# ServoControllerCircuit.net
KiCad netlist of a schematic drawn in EAGLE
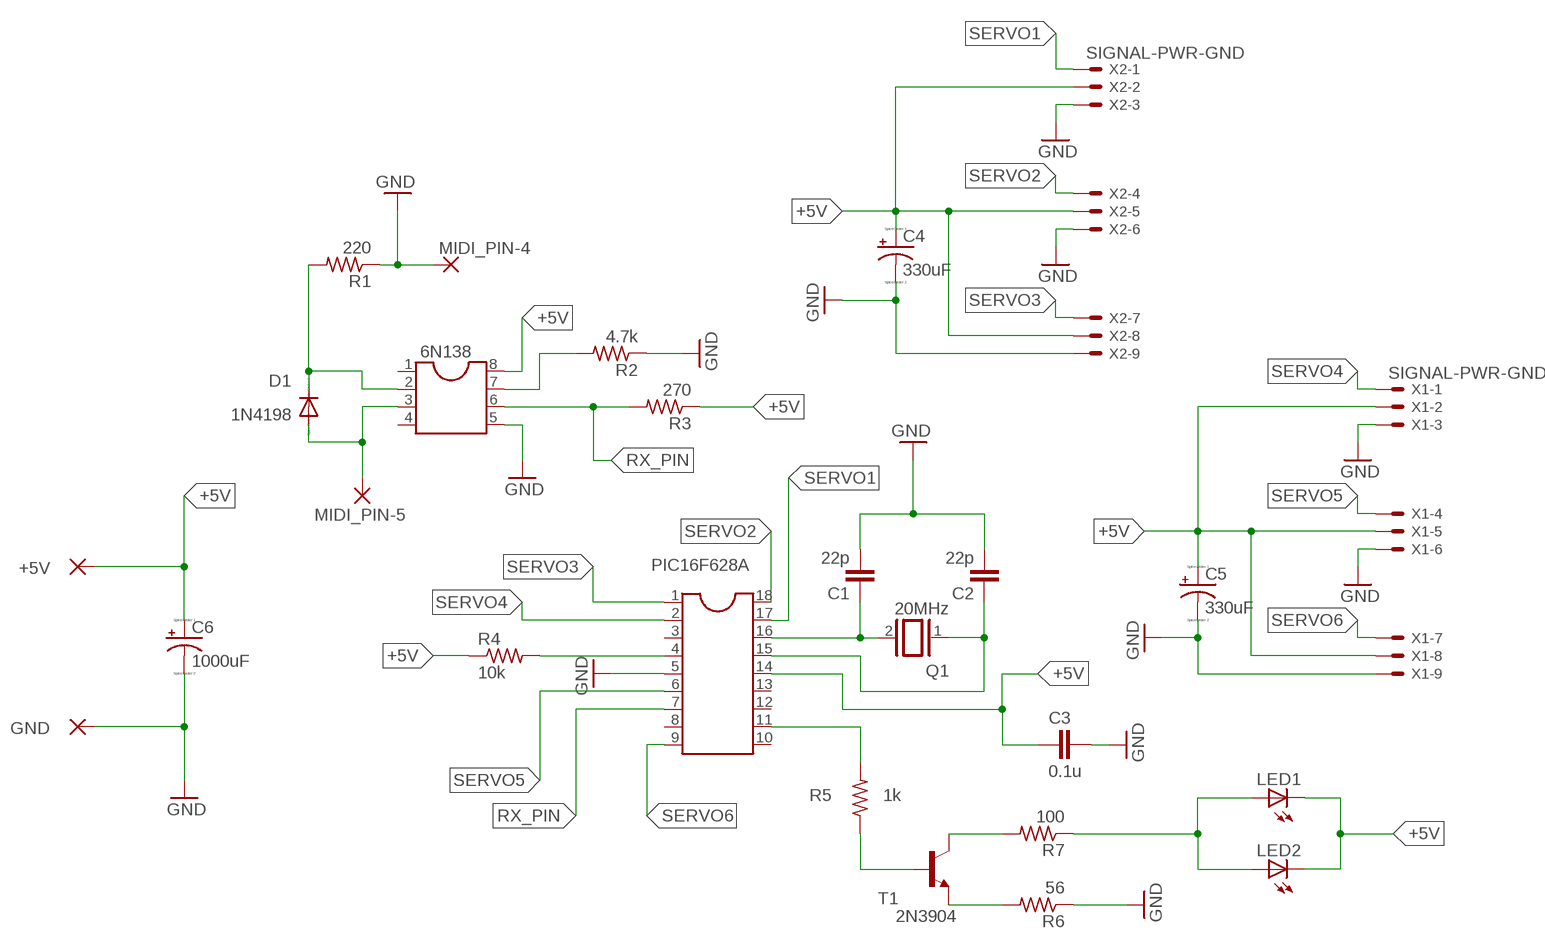
[diagram p0: schematic, sheet 1]

(export (version "E")
  (design (tool "Eeschema 10.0.6"))
  (components
    (comp (ref "+5V")
      (value "2,15/1,0")
      (footprint "eagle-import:2,15_1,0")
      (libsource (lib "eagle-import") (part "2,15/1,0"))
    )
    (comp (ref "6N138")
      (value "DIL8S")
      (footprint "eagle-import:SOCKET-08")
      (libsource (lib "eagle-import") (part "DIL8S"))
    )
    (comp (ref "C1")
      (value "22p")
      (footprint "eagle-import:C050-025X075")
      (libsource (lib "eagle-import") (part "C-EU050-025X075"))
    )
    (comp (ref "C2")
      (value "22p")
      (footprint "eagle-import:C050-025X075")
      (libsource (lib "eagle-import") (part "C-EU050-025X075"))
    )
    (comp (ref "C3")
      (value "0.1u")
      (footprint "eagle-import:C050-025X075")
      (libsource (lib "eagle-import") (part "C-EU050-025X075"))
    )
    (comp (ref "C4")
      (value "330uF")
      (footprint "eagle-import:E3,5-8")
      (libsource (lib "eagle-import") (part "CPOL-USE3.5-8"))
    )
    (comp (ref "C5")
      (value "330uF")
      (footprint "eagle-import:E3,5-8")
      (libsource (lib "eagle-import") (part "CPOL-USE3.5-8"))
    )
    (comp (ref "C6")
      (value "1000uF")
      (footprint "eagle-import:E5-10,5")
      (libsource (lib "eagle-import") (part "CPOL-USE5-10.5"))
    )
    (comp (ref "D1")
      (value "1N4198")
      (footprint "eagle-import:DO35-10")
      (libsource (lib "eagle-import") (part "1N4148DO35-10"))
    )
    (comp (ref "GND")
      (value "2,15/1,0")
      (footprint "eagle-import:2,15_1,0")
      (libsource (lib "eagle-import") (part "2,15/1,0"))
    )
    (comp (ref "LED1")
      (value "LED5MM")
      (footprint "eagle-import:LED5MM")
      (libsource (lib "eagle-import") (part "LED5MM"))
    )
    (comp (ref "LED2")
      (value "LED5MM")
      (footprint "eagle-import:LED5MM")
      (libsource (lib "eagle-import") (part "LED5MM"))
    )
    (comp (ref "MIDI_PIN-4")
      (value "2,15/1,0")
      (footprint "eagle-import:2,15_1,0")
      (libsource (lib "eagle-import") (part "2,15/1,0"))
    )
    (comp (ref "MIDI_PIN-5")
      (value "2,15/1,0")
      (footprint "eagle-import:2,15_1,0")
      (libsource (lib "eagle-import") (part "2,15/1,0"))
    )
    (comp (ref "PIC16F628A")
      (value "DIL18S")
      (footprint "eagle-import:SOCKET-18")
      (libsource (lib "eagle-import") (part "DIL18S"))
    )
    (comp (ref "Q1")
      (value "20MHz")
      (footprint "eagle-import:QS")
      (libsource (lib "eagle-import") (part "XTAL/S"))
    )
    (comp (ref "R1")
      (value "220")
      (footprint "eagle-import:0207_12")
      (libsource (lib "eagle-import") (part "R-US_0207/12"))
    )
    (comp (ref "R2")
      (value "4.7k")
      (footprint "eagle-import:0207_12")
      (libsource (lib "eagle-import") (part "R-US_0207/12"))
    )
    (comp (ref "R3")
      (value "270")
      (footprint "eagle-import:0207_12")
      (libsource (lib "eagle-import") (part "R-US_0207/12"))
    )
    (comp (ref "R4")
      (value "10k")
      (footprint "eagle-import:0207_12")
      (libsource (lib "eagle-import") (part "R-US_0207/12"))
    )
    (comp (ref "R5")
      (value "1k")
      (footprint "eagle-import:0207_12")
      (libsource (lib "eagle-import") (part "R-US_0207/12"))
    )
    (comp (ref "R6")
      (value "56")
      (footprint "eagle-import:0207_12")
      (libsource (lib "eagle-import") (part "R-US_0207/12"))
    )
    (comp (ref "R7")
      (value "100")
      (footprint "eagle-import:0207_12")
      (libsource (lib "eagle-import") (part "R-US_0207/12"))
    )
    (comp (ref "T1")
      (value "2N3904")
      (footprint "eagle-import:TO92")
      (libsource (lib "eagle-import") (part "2N3904"))
    )
    (comp (ref "X1")
      (value "SIGNAL-PWR-GND")
      (footprint "eagle-import:22-23-2091")
      (fields (field (name "MF") "MOLEX") (field (name "MPN") "22-23-2091"))
      (libsource (lib "eagle-import") (part "22-23-2091"))
    )
    (comp (ref "X2")
      (value "SIGNAL-PWR-GND")
      (footprint "eagle-import:22-23-2091")
      (fields (field (name "MF") "MOLEX") (field (name "MPN") "22-23-2091"))
      (libsource (lib "eagle-import") (part "22-23-2091"))
    )
  )
  (nets
    (net (code "1") (name "+5V") (class "Default")
      (node (ref "+5V") (pin "1") (pinfunction "P_1") (pintype "passive"))
      (node (ref "6N138") (pin "8") (pinfunction "8_8") (pintype "passive"))
      (node (ref "C3") (pin "2") (pinfunction "2_2") (pintype "passive"))
      (node (ref "C4") (pin "+") (pinfunction "+_+") (pintype "passive"))
      (node (ref "C5") (pin "+") (pinfunction "+_+") (pintype "passive"))
      (node (ref "C6") (pin "+") (pinfunction "+_+") (pintype "passive"))
      (node (ref "LED1") (pin "K") (pinfunction "C_K") (pintype "passive"))
      (node (ref "LED2") (pin "K") (pinfunction "C_K") (pintype "passive"))
      (node (ref "PIC16F628A") (pin "14") (pinfunction "14_14") (pintype "passive"))
      (node (ref "R3") (pin "1") (pinfunction "1_1") (pintype "passive"))
      (node (ref "R4") (pin "1") (pinfunction "1_1") (pintype "passive"))
      (node (ref "X1") (pin "2") (pinfunction "S_2") (pintype "passive"))
      (node (ref "X1") (pin "5") (pinfunction "S_5") (pintype "passive"))
      (node (ref "X1") (pin "8") (pinfunction "S_8") (pintype "passive"))
      (node (ref "X2") (pin "2") (pinfunction "S_2") (pintype "passive"))
      (node (ref "X2") (pin "5") (pinfunction "S_5") (pintype "passive"))
      (node (ref "X2") (pin "8") (pinfunction "S_8") (pintype "passive"))
    )
    (net (code "2") (name "GND") (class "Default")
      (node (ref "6N138") (pin "5") (pinfunction "5_5") (pintype "passive"))
      (node (ref "C1") (pin "2") (pinfunction "2_2") (pintype "passive"))
      (node (ref "C2") (pin "2") (pinfunction "2_2") (pintype "passive"))
      (node (ref "C3") (pin "1") (pinfunction "1_1") (pintype "passive"))
      (node (ref "C4") (pin "-") (pinfunction "-_-") (pintype "passive"))
      (node (ref "C5") (pin "-") (pinfunction "-_-") (pintype "passive"))
      (node (ref "C6") (pin "-") (pinfunction "-_-") (pintype "passive"))
      (node (ref "GND") (pin "1") (pinfunction "P_1") (pintype "passive"))
      (node (ref "MIDI_PIN-4") (pin "1") (pinfunction "P_1") (pintype "passive"))
      (node (ref "PIC16F628A") (pin "5") (pinfunction "5_5") (pintype "passive"))
      (node (ref "R1") (pin "1") (pinfunction "1_1") (pintype "passive"))
      (node (ref "R2") (pin "1") (pinfunction "1_1") (pintype "passive"))
      (node (ref "R6") (pin "1") (pinfunction "1_1") (pintype "passive"))
      (node (ref "X1") (pin "3") (pinfunction "S_3") (pintype "passive"))
      (node (ref "X1") (pin "6") (pinfunction "S_6") (pintype "passive"))
      (node (ref "X1") (pin "9") (pinfunction "S_9") (pintype "passive"))
      (node (ref "X2") (pin "3") (pinfunction "S_3") (pintype "passive"))
      (node (ref "X2") (pin "6") (pinfunction "S_6") (pintype "passive"))
      (node (ref "X2") (pin "9") (pinfunction "S_9") (pintype "passive"))
    )
    (net (code "3") (name "Net-(6N138-Pad2)") (class "Default")
      (node (ref "6N138") (pin "2") (pinfunction "2_2") (pintype "passive"))
      (node (ref "D1") (pin "C") (pinfunction "C_C") (pintype "passive"))
      (node (ref "R1") (pin "2") (pinfunction "2_2") (pintype "passive"))
    )
    (net (code "4") (name "Net-(6N138-Pad7)") (class "Default")
      (node (ref "6N138") (pin "7") (pinfunction "7_7") (pintype "passive"))
      (node (ref "R2") (pin "2") (pinfunction "2_2") (pintype "passive"))
    )
    (net (code "5") (name "Net-(C1-Pad1)") (class "Default")
      (node (ref "C1") (pin "1") (pinfunction "1_1") (pintype "passive"))
      (node (ref "PIC16F628A") (pin "16") (pinfunction "16_16") (pintype "passive"))
      (node (ref "Q1") (pin "2") (pinfunction "2_2") (pintype "passive"))
    )
    (net (code "6") (name "Net-(C2-Pad1)") (class "Default")
      (node (ref "C2") (pin "1") (pinfunction "1_1") (pintype "passive"))
      (node (ref "PIC16F628A") (pin "15") (pinfunction "15_15") (pintype "passive"))
      (node (ref "Q1") (pin "1") (pinfunction "1_1") (pintype "passive"))
    )
    (net (code "7") (name "Net-(LED1-PadA)") (class "Default")
      (node (ref "LED1") (pin "A") (pinfunction "A_A") (pintype "passive"))
      (node (ref "LED2") (pin "A") (pinfunction "A_A") (pintype "passive"))
      (node (ref "R7") (pin "1") (pinfunction "1_1") (pintype "passive"))
    )
    (net (code "8") (name "Net-(MIDI_PIN-5-P)") (class "Default")
      (node (ref "6N138") (pin "3") (pinfunction "3_3") (pintype "passive"))
      (node (ref "D1") (pin "A") (pinfunction "A_A") (pintype "passive"))
      (node (ref "MIDI_PIN-5") (pin "1") (pinfunction "P_1") (pintype "passive"))
    )
    (net (code "9") (name "Net-(PIC16F628A-Pad4)") (class "Default")
      (node (ref "PIC16F628A") (pin "4") (pinfunction "4_4") (pintype "passive"))
      (node (ref "R4") (pin "2") (pinfunction "2_2") (pintype "passive"))
    )
    (net (code "10") (name "Net-(PIC16F628A-Pad11)") (class "Default")
      (node (ref "PIC16F628A") (pin "11") (pinfunction "11_11") (pintype "passive"))
      (node (ref "R5") (pin "2") (pinfunction "2_2") (pintype "passive"))
    )
    (net (code "11") (name "Net-(T1-B)") (class "Default")
      (node (ref "R5") (pin "1") (pinfunction "1_1") (pintype "passive"))
      (node (ref "T1") (pin "2") (pinfunction "B_2") (pintype "passive"))
    )
    (net (code "12") (name "Net-(T1-C)") (class "Default")
      (node (ref "R7") (pin "2") (pinfunction "2_2") (pintype "passive"))
      (node (ref "T1") (pin "1") (pinfunction "C_1") (pintype "passive"))
    )
    (net (code "13") (name "Net-(T1-E)") (class "Default")
      (node (ref "R6") (pin "2") (pinfunction "2_2") (pintype "passive"))
      (node (ref "T1") (pin "3") (pinfunction "E_3") (pintype "passive"))
    )
    (net (code "14") (name "RX_PIN") (class "Default")
      (node (ref "6N138") (pin "6") (pinfunction "6_6") (pintype "passive"))
      (node (ref "PIC16F628A") (pin "7") (pinfunction "7_7") (pintype "passive"))
      (node (ref "R3") (pin "2") (pinfunction "2_2") (pintype "passive"))
    )
    (net (code "15") (name "SERVO1") (class "Default")
      (node (ref "PIC16F628A") (pin "17") (pinfunction "17_17") (pintype "passive"))
      (node (ref "X2") (pin "1") (pinfunction "S_1") (pintype "passive"))
    )
    (net (code "16") (name "SERVO2") (class "Default")
      (node (ref "PIC16F628A") (pin "18") (pinfunction "18_18") (pintype "passive"))
      (node (ref "X2") (pin "4") (pinfunction "S_4") (pintype "passive"))
    )
    (net (code "17") (name "SERVO3") (class "Default")
      (node (ref "PIC16F628A") (pin "1") (pinfunction "1_1") (pintype "passive"))
      (node (ref "X2") (pin "7") (pinfunction "S_7") (pintype "passive"))
    )
    (net (code "18") (name "SERVO4") (class "Default")
      (node (ref "PIC16F628A") (pin "2") (pinfunction "2_2") (pintype "passive"))
      (node (ref "X1") (pin "1") (pinfunction "S_1") (pintype "passive"))
    )
    (net (code "19") (name "SERVO5") (class "Default")
      (node (ref "PIC16F628A") (pin "6") (pinfunction "6_6") (pintype "passive"))
      (node (ref "X1") (pin "4") (pinfunction "S_4") (pintype "passive"))
    )
    (net (code "20") (name "SERVO6") (class "Default")
      (node (ref "PIC16F628A") (pin "9") (pinfunction "9_9") (pintype "passive"))
      (node (ref "X1") (pin "7") (pinfunction "S_7") (pintype "passive"))
    )
    (net (code "21") (name "unconnected-(6N138-Pad1)") (class "Default")
      (node (ref "6N138") (pin "1") (pinfunction "1_1") (pintype "passive"))
    )
    (net (code "22") (name "unconnected-(6N138-Pad4)") (class "Default")
      (node (ref "6N138") (pin "4") (pinfunction "4_4") (pintype "passive"))
    )
    (net (code "23") (name "unconnected-(PIC16F628A-Pad3)") (class "Default")
      (node (ref "PIC16F628A") (pin "3") (pinfunction "3_3") (pintype "passive"))
    )
    (net (code "24") (name "unconnected-(PIC16F628A-Pad8)") (class "Default")
      (node (ref "PIC16F628A") (pin "8") (pinfunction "8_8") (pintype "passive"))
    )
    (net (code "25") (name "unconnected-(PIC16F628A-Pad10)") (class "Default")
      (node (ref "PIC16F628A") (pin "10") (pinfunction "10_10") (pintype "passive"))
    )
    (net (code "26") (name "unconnected-(PIC16F628A-Pad12)") (class "Default")
      (node (ref "PIC16F628A") (pin "12") (pinfunction "12_12") (pintype "passive"))
    )
    (net (code "27") (name "unconnected-(PIC16F628A-Pad13)") (class "Default")
      (node (ref "PIC16F628A") (pin "13") (pinfunction "13_13") (pintype "passive"))
    )
  )
)
